# telem_gsm.net
KiCad netlist of a schematic drawn in Altium Designer
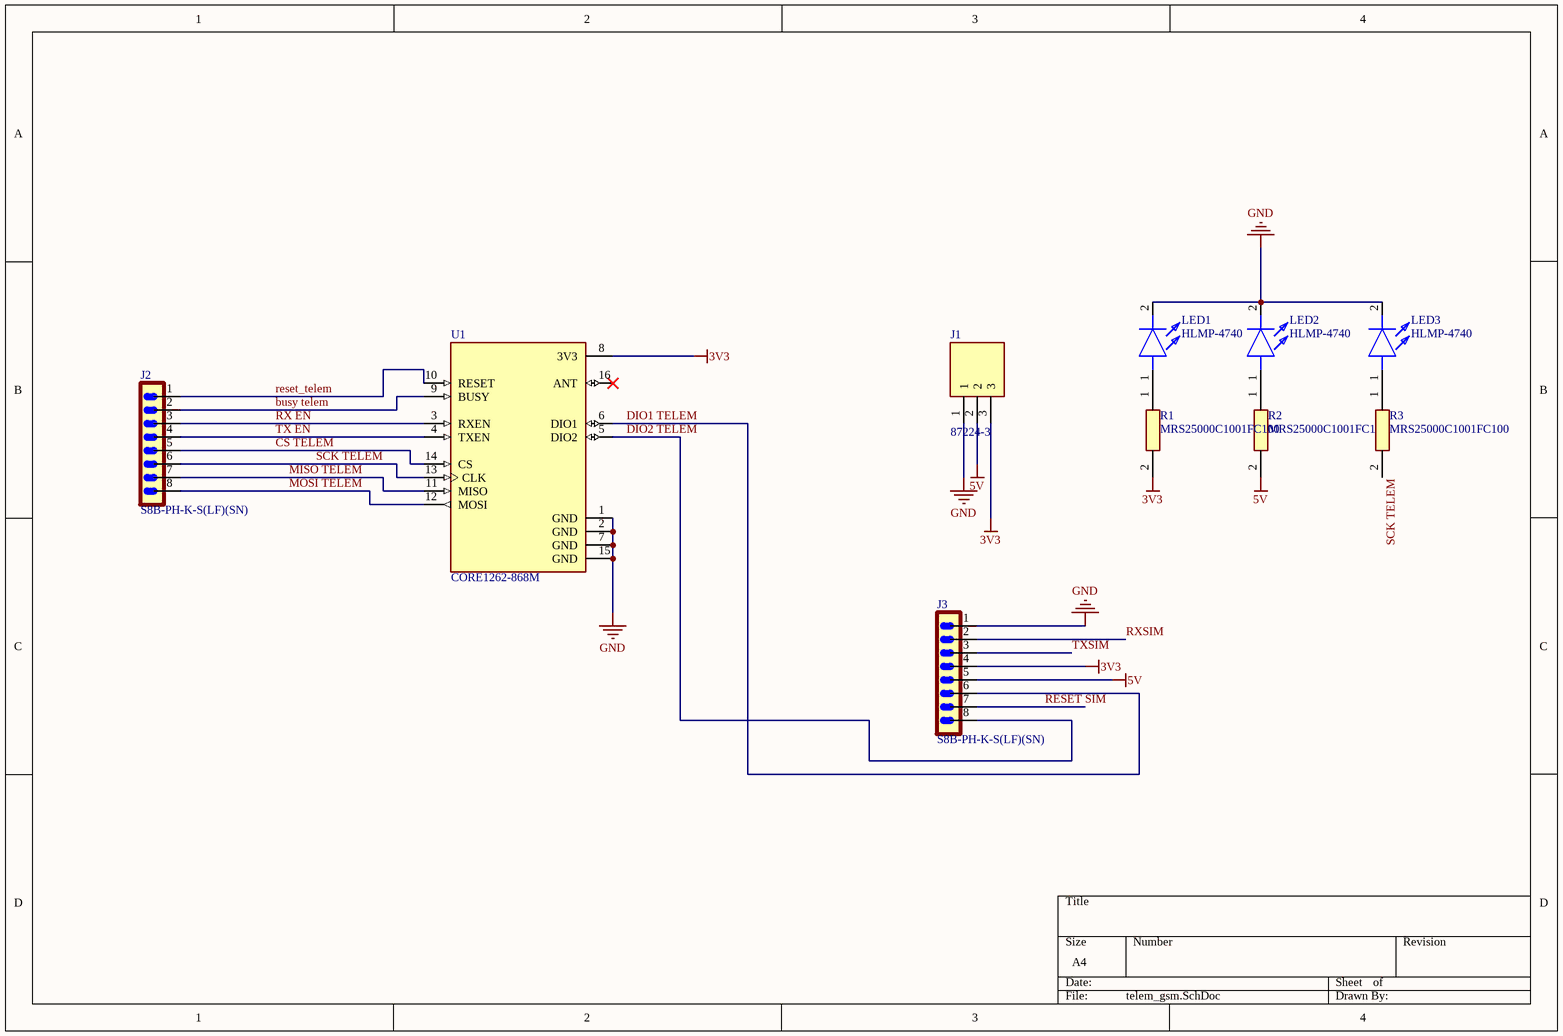
[diagram p0: telem_gsm.SchDoc]

(export (version "E")
  (design (tool "Eeschema 10.0.6"))
  (components
    (comp (ref "J1")
      (value "87224-3")
      (footprint "SamacSys:872243")
      (description "Connector")
      (fields (field (name "MOUSER PART NUMBER") "571-872243"))
      (libsource (lib "SamacSys") (part "87224-3"))
    )
    (comp (ref "J2")
      (value "S8B-PH-K-S(LF)(SN)")
      (footprint "DW08R")
      (description "ç©´ã‚’é€šã‚‹ã‚³ãƒã‚¯ã‚¿ãƒ˜ãƒƒãƒ€ãƒ¼ã€å³è§’åº¦8ä½ç½®0.079 (2.00mm)ã€‚")
      (fields (field (name "MF") "JST Sales") (field (name "MP") "S8B-PH-K-S (LF)(SN)"))
      (libsource (lib "S8B-PH-K-S(LF)(SN)") (part "S8B-PH-K-S(LF)(SN)"))
    )
    (comp (ref "J3")
      (value "S8B-PH-K-S(LF)(SN)")
      (footprint "DW08R")
      (description "ç©´ã‚’é€šã‚‹ã‚³ãƒã‚¯ã‚¿ãƒ˜ãƒƒãƒ€ãƒ¼ã€å³è§’åº¦8ä½ç½®0.079 (2.00mm)ã€‚")
      (fields (field (name "MF") "JST Sales") (field (name "MP") "S8B-PH-K-S (LF)(SN)"))
      (libsource (lib "S8B-PH-K-S(LF)(SN)") (part "S8B-PH-K-S(LF)(SN)"))
    )
    (comp (ref "LED1")
      (value "HLMP-4740")
      (footprint "SamacSys:HLMP4740")
      (description "LED")
      (fields (field (name "MOUSER PART NUMBER") "630-HLMP-4740"))
      (libsource (lib "SamacSys") (part "HLMP-4740"))
    )
    (comp (ref "LED2")
      (value "HLMP-4740")
      (footprint "SamacSys:HLMP4740")
      (description "LED")
      (fields (field (name "MOUSER PART NUMBER") "630-HLMP-4740"))
      (libsource (lib "SamacSys") (part "HLMP-4740"))
    )
    (comp (ref "LED3")
      (value "HLMP-4740")
      (footprint "SamacSys:HLMP4740")
      (description "LED")
      (fields (field (name "MOUSER PART NUMBER") "630-HLMP-4740"))
      (libsource (lib "SamacSys") (part "HLMP-4740"))
    )
    (comp (ref "R1")
      (value "MRS25000C1001FC100")
      (footprint "SamacSys:RESAD1650W60L650D250")
      (description "Resistor")
      (fields (field (name "MOUSER PART NUMBER") "594-MRS25000C1001FC1"))
      (libsource (lib "SamacSys") (part "MRS25000C1001FC100"))
    )
    (comp (ref "R2")
      (value "MRS25000C1001FC100")
      (footprint "SamacSys:RESAD1650W60L650D250")
      (description "Resistor")
      (fields (field (name "MOUSER PART NUMBER") "594-MRS25000C1001FC1"))
      (libsource (lib "SamacSys") (part "MRS25000C1001FC100"))
    )
    (comp (ref "R3")
      (value "MRS25000C1001FC100")
      (footprint "SamacSys:RESAD1650W60L650D250")
      (description "Resistor")
      (fields (field (name "MOUSER PART NUMBER") "594-MRS25000C1001FC1"))
      (libsource (lib "SamacSys") (part "MRS25000C1001FC100"))
    )
    (comp (ref "U1")
      (value "CORE1262-868M")
      (footprint "XCVR_CORE1262-868M")
      (description "Lora core module")
      (fields (field (name "MF") "Waveshare Electronics") (field (name "MP") "Core1262-868M"))
      (libsource (lib "SX1262") (part "CORE1262-868M"))
    )
  )
  (nets
    (net (code "1") (name "/CS TELEM") (class "Default")
      (node (ref "J2") (pin "5") (pinfunction "5_5") (pintype "passive"))
      (node (ref "U1") (pin "14") (pinfunction "CS_14") (pintype "input"))
    )
    (net (code "2") (name "/DIO1 TELEM") (class "Default")
      (node (ref "J3") (pin "6") (pinfunction "6_6") (pintype "passive"))
      (node (ref "U1") (pin "6") (pinfunction "DIO1_6") (pintype "bidirectional"))
    )
    (net (code "3") (name "/DIO2 TELEM") (class "Default")
      (node (ref "J3") (pin "8") (pinfunction "8_8") (pintype "passive"))
      (node (ref "U1") (pin "5") (pinfunction "DIO2_5") (pintype "bidirectional"))
    )
    (net (code "4") (name "/MISO TELEM") (class "Default")
      (node (ref "J2") (pin "7") (pinfunction "7_7") (pintype "passive"))
      (node (ref "U1") (pin "11") (pinfunction "MISO_11") (pintype "input"))
    )
    (net (code "5") (name "/MOSI TELEM") (class "Default")
      (node (ref "J2") (pin "8") (pinfunction "8_8") (pintype "passive"))
      (node (ref "U1") (pin "12") (pinfunction "MOSI_12") (pintype "output"))
    )
    (net (code "6") (name "/RESET SIM") (class "Default")
      (node (ref "J3") (pin "7") (pinfunction "7_7") (pintype "passive"))
    )
    (net (code "7") (name "/RX EN") (class "Default")
      (node (ref "J2") (pin "3") (pinfunction "3_3") (pintype "passive"))
      (node (ref "U1") (pin "3") (pinfunction "RXEN_3") (pintype "input"))
    )
    (net (code "8") (name "/RXSIM") (class "Default")
      (node (ref "J3") (pin "2") (pinfunction "2_2") (pintype "passive"))
    )
    (net (code "9") (name "/SCK TELEM") (class "Default")
      (node (ref "J2") (pin "6") (pinfunction "6_6") (pintype "passive"))
      (node (ref "R3") (pin "2") (pinfunction "2_2") (pintype "passive"))
      (node (ref "U1") (pin "13") (pinfunction "CLK_13") (pintype "input"))
    )
    (net (code "10") (name "/TX EN") (class "Default")
      (node (ref "J2") (pin "4") (pinfunction "4_4") (pintype "passive"))
      (node (ref "U1") (pin "4") (pinfunction "TXEN_4") (pintype "input"))
    )
    (net (code "11") (name "/TXSIM") (class "Default")
      (node (ref "J3") (pin "3") (pinfunction "3_3") (pintype "passive"))
    )
    (net (code "12") (name "/busy telem") (class "Default")
      (node (ref "J2") (pin "2") (pinfunction "2_2") (pintype "passive"))
      (node (ref "U1") (pin "9") (pinfunction "BUSY_9") (pintype "input"))
    )
    (net (code "13") (name "/reset_telem") (class "Default")
      (node (ref "J2") (pin "1") (pinfunction "1_1") (pintype "passive"))
      (node (ref "U1") (pin "10") (pinfunction "RESET_10") (pintype "input"))
    )
    (net (code "14") (name "3V3") (class "Default")
      (node (ref "J1") (pin "3") (pinfunction "3_3") (pintype "passive"))
      (node (ref "J3") (pin "4") (pinfunction "4_4") (pintype "passive"))
      (node (ref "R1") (pin "2") (pinfunction "2_2") (pintype "passive"))
      (node (ref "U1") (pin "8") (pinfunction "3V3_8") (pintype "power_in"))
    )
    (net (code "15") (name "5V") (class "Default")
      (node (ref "J1") (pin "2") (pinfunction "2_2") (pintype "passive"))
      (node (ref "J3") (pin "5") (pinfunction "5_5") (pintype "passive"))
      (node (ref "R2") (pin "2") (pinfunction "2_2") (pintype "passive"))
    )
    (net (code "16") (name "GND") (class "Default")
      (node (ref "J1") (pin "1") (pinfunction "1_1") (pintype "passive"))
      (node (ref "J3") (pin "1") (pinfunction "1_1") (pintype "passive"))
      (node (ref "LED1") (pin "2") (pinfunction "K_2") (pintype "passive"))
      (node (ref "LED2") (pin "2") (pinfunction "K_2") (pintype "passive"))
      (node (ref "LED3") (pin "2") (pinfunction "K_2") (pintype "passive"))
      (node (ref "U1") (pin "1") (pinfunction "GND_1") (pintype "power_in"))
      (node (ref "U1") (pin "15") (pinfunction "GND_15") (pintype "power_in"))
      (node (ref "U1") (pin "2") (pinfunction "GND_2") (pintype "power_in"))
      (node (ref "U1") (pin "7") (pinfunction "GND_7") (pintype "power_in"))
    )
    (net (code "17") (name "Net-(LED1-A)") (class "Default")
      (node (ref "LED1") (pin "1") (pinfunction "A_1") (pintype "passive"))
      (node (ref "R1") (pin "1") (pinfunction "1_1") (pintype "passive"))
    )
    (net (code "18") (name "Net-(LED2-A)") (class "Default")
      (node (ref "LED2") (pin "1") (pinfunction "A_1") (pintype "passive"))
      (node (ref "R2") (pin "1") (pinfunction "1_1") (pintype "passive"))
    )
    (net (code "19") (name "Net-(LED3-A)") (class "Default")
      (node (ref "LED3") (pin "1") (pinfunction "A_1") (pintype "passive"))
      (node (ref "R3") (pin "1") (pinfunction "1_1") (pintype "passive"))
    )
    (net (code "20") (name "unconnected-(U1-ANT-Pad16)") (class "Default")
      (node (ref "U1") (pin "16") (pinfunction "ANT_16") (pintype "bidirectional+no_connect"))
    )
  )
)
